# LoRa_Node_Schematic.net
KiCad netlist of a schematic drawn in EAGLE
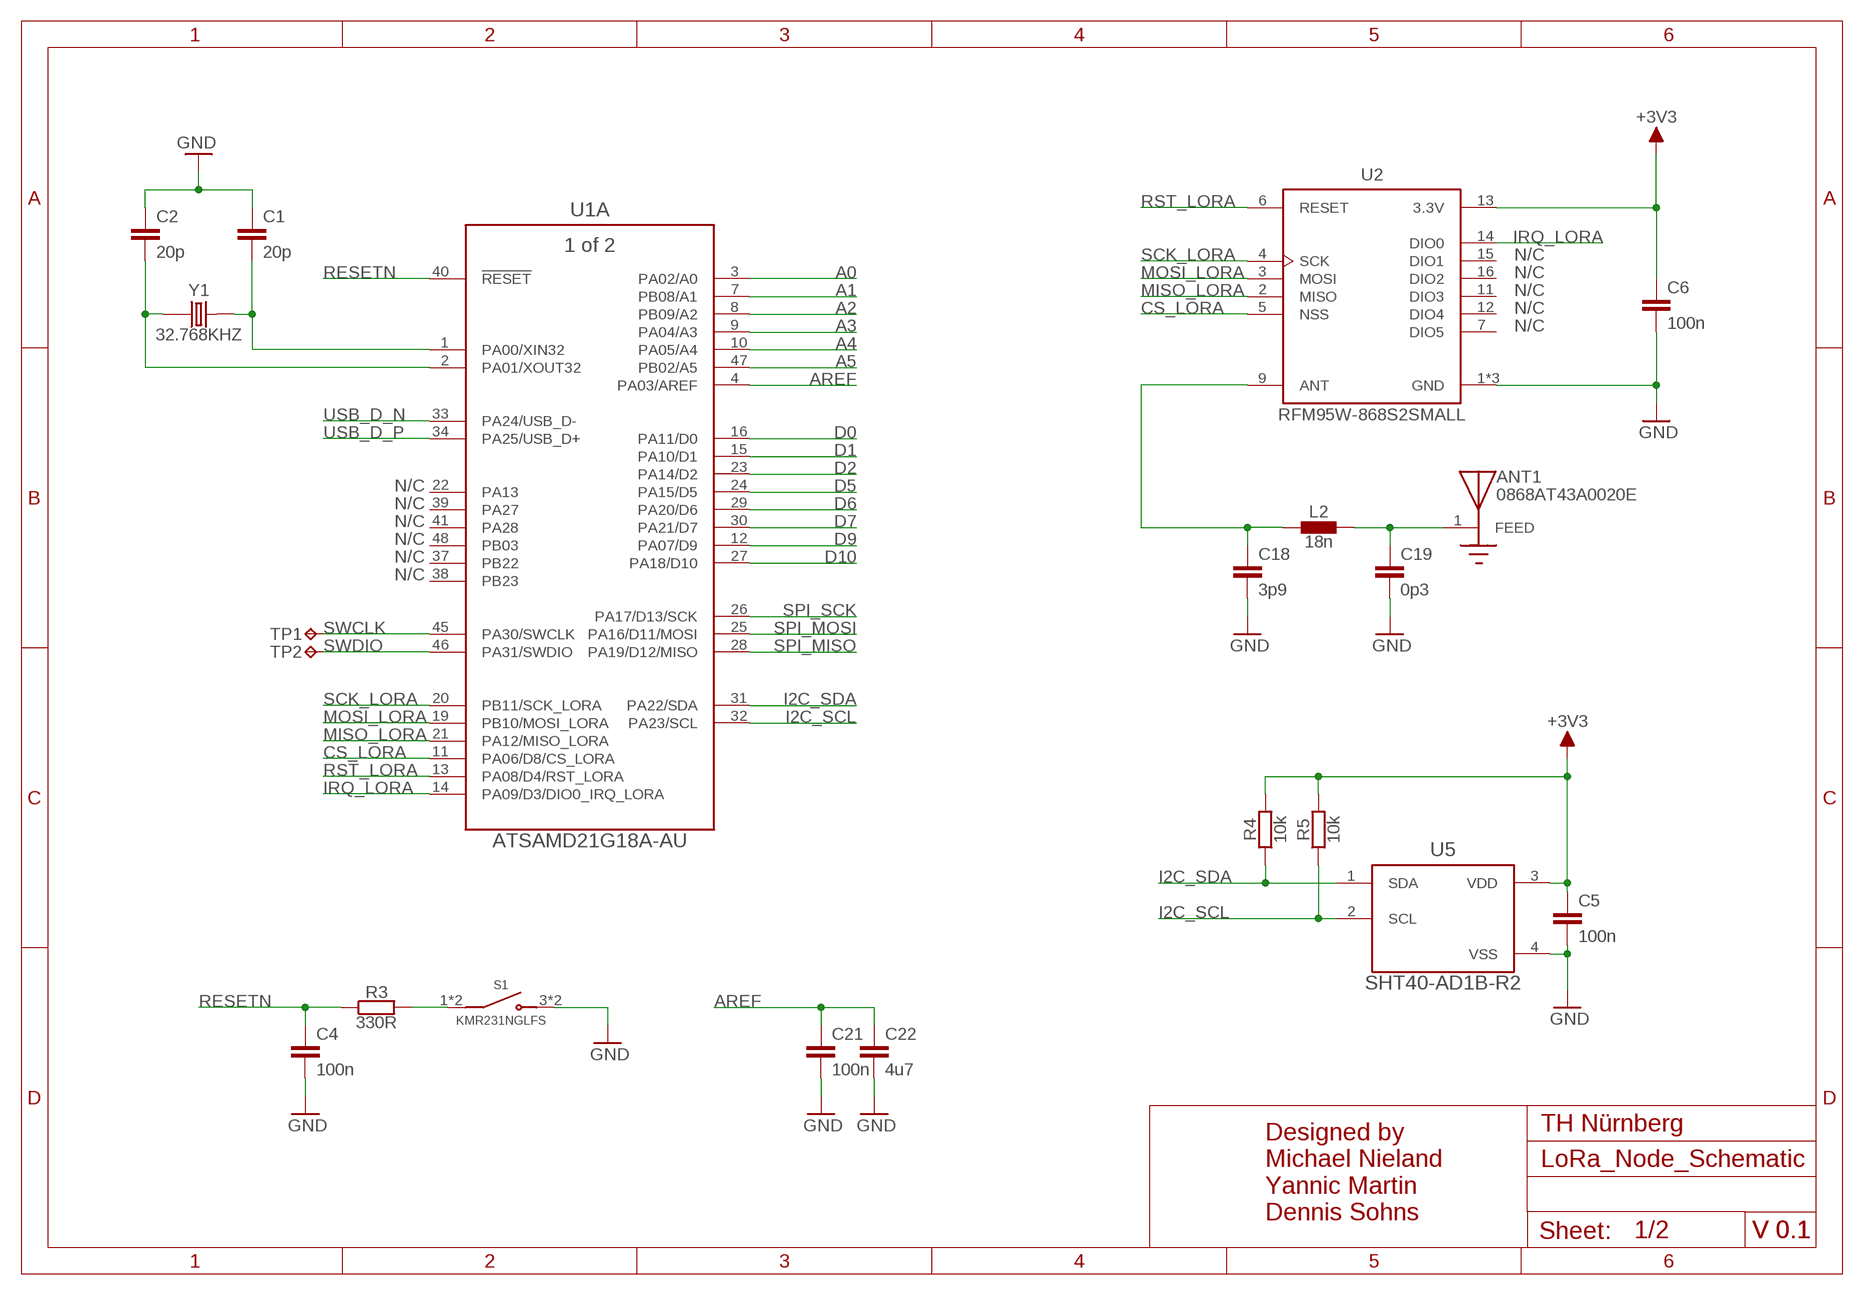
[diagram p0: schematic, sheet 1]
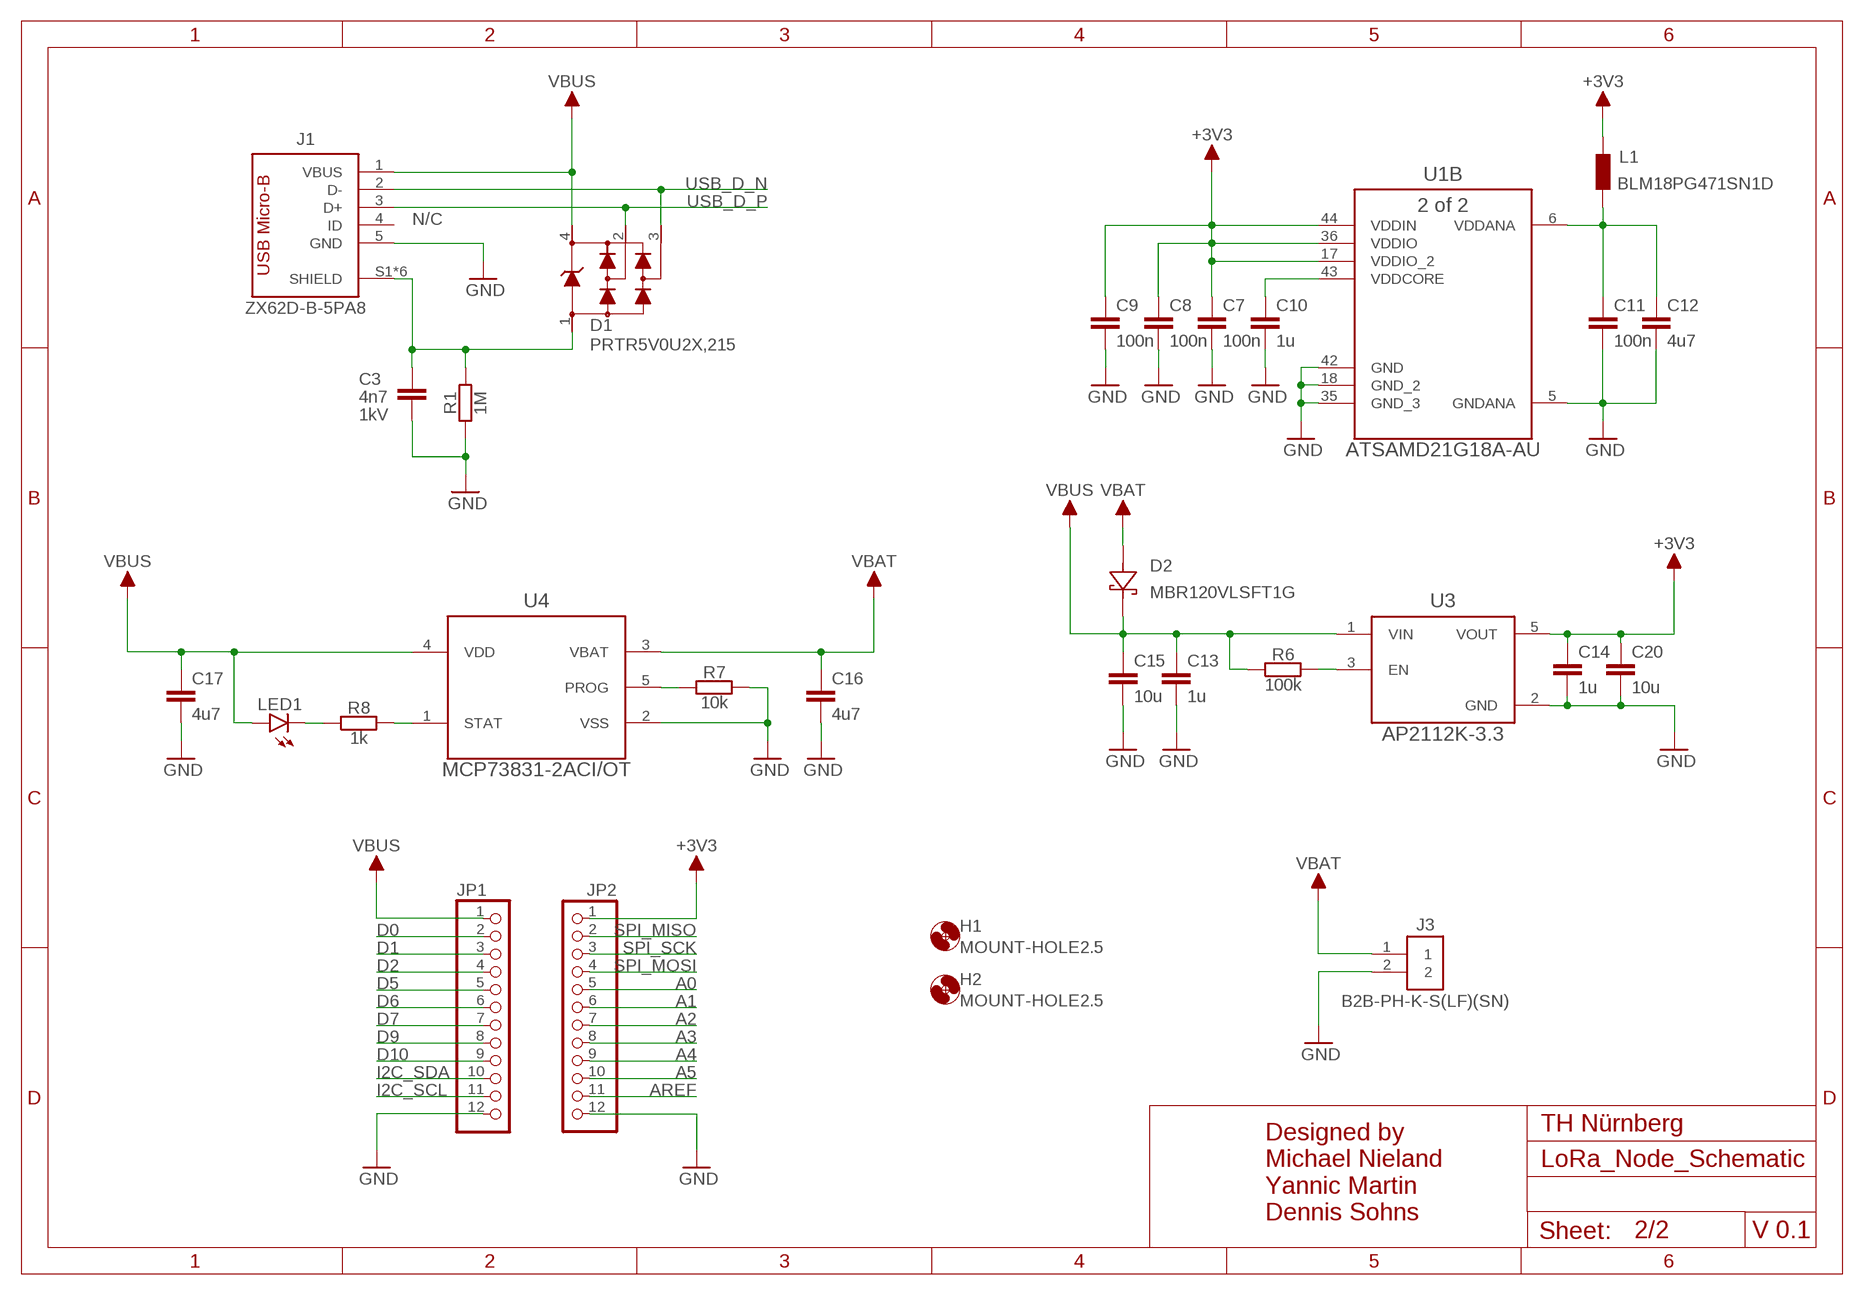
[diagram p1: schematic, sheet 2]

(export (version "E")
  (design (tool "Eeschema 10.0.6"))
  (components
    (comp (ref "C3")
      (value "4n7")
      (footprint "eagle-import:C0805")
      (fields (field (name "MANUFACTURER") "KEMET") (field (name "VOLTAGE") "1kV"))
      (libsource (lib "eagle-import") (part "C-EUC0805"))
    )
    (comp (ref "C7")
      (value "100n")
      (footprint "eagle-import:C0402")
      (libsource (lib "eagle-import") (part "C-EUC0402"))
    )
    (comp (ref "C8")
      (value "100n")
      (footprint "eagle-import:C0402")
      (libsource (lib "eagle-import") (part "C-EUC0402"))
    )
    (comp (ref "C9")
      (value "100n")
      (footprint "eagle-import:C0402")
      (libsource (lib "eagle-import") (part "C-EUC0402"))
    )
    (comp (ref "C10")
      (value "1u")
      (footprint "eagle-import:C0402")
      (libsource (lib "eagle-import") (part "C-EUC0402"))
    )
    (comp (ref "C11")
      (value "100n")
      (footprint "eagle-import:C0402")
      (libsource (lib "eagle-import") (part "C-EUC0402"))
    )
    (comp (ref "C12")
      (value "4u7")
      (footprint "eagle-import:C0603")
      (libsource (lib "eagle-import") (part "C-EUC0603"))
    )
    (comp (ref "C13")
      (value "1u")
      (footprint "eagle-import:C0402")
      (libsource (lib "eagle-import") (part "C-EUC0402"))
    )
    (comp (ref "C14")
      (value "1u")
      (footprint "eagle-import:C0402")
      (libsource (lib "eagle-import") (part "C-EUC0402"))
    )
    (comp (ref "C15")
      (value "10u")
      (footprint "eagle-import:C0603")
      (libsource (lib "eagle-import") (part "C-EUC0603"))
    )
    (comp (ref "C16")
      (value "4u7")
      (footprint "eagle-import:C0603")
      (libsource (lib "eagle-import") (part "C-EUC0603"))
    )
    (comp (ref "C17")
      (value "4u7")
      (footprint "eagle-import:C0603")
      (libsource (lib "eagle-import") (part "C-EUC0603"))
    )
    (comp (ref "C20")
      (value "10u")
      (footprint "eagle-import:C0603")
      (libsource (lib "eagle-import") (part "C-EUC0603"))
    )
    (comp (ref "D1")
      (value "PRTR5V0U2X,215")
      (footprint "eagle-import:SOT143B")
      (fields (field (name "MF") "Nexperia USA Inc."))
      (libsource (lib "eagle-import") (part "PRTR5V0U2X,215"))
    )
    (comp (ref "D2")
      (value "MBR120VLSFT1G")
      (footprint "eagle-import:SDO_SOD-123FL_ONS")
      (fields (field (name "COPYRIGHT") "Copyright (C) 2018 Accelerated Designs. All rights reserved"))
      (libsource (lib "eagle-import") (part "MBR120VLSFT1G"))
    )
    (comp (ref "H1")
      (value "MOUNT-HOLE2.5")
      (footprint "eagle-import:MICROBUILDER_MOUNTINGHOLE_2.5_PLATED")
      (libsource (lib "eagle-import") (part "MOUNT-HOLE2.5"))
    )
    (comp (ref "H2")
      (value "MOUNT-HOLE2.5")
      (footprint "eagle-import:MICROBUILDER_MOUNTINGHOLE_2.5_PLATED")
      (libsource (lib "eagle-import") (part "MOUNT-HOLE2.5"))
    )
    (comp (ref "J1")
      (value "ZX62D-B-5PA8")
      (footprint "eagle-import:HIROSE_ZX62D-B-5PA8")
      (fields (field (name "MF") "Hirose"))
      (libsource (lib "eagle-import") (part "ZX62D-B-5PA8"))
    )
    (comp (ref "J3")
      (value "B2B-PH-K-S(LF)(SN)")
      (footprint "eagle-import:JST_B2B-PH-K-S(LF)(SN)")
      (fields (field (name "MF") "JST Sales"))
      (libsource (lib "eagle-import") (part "B2B-PH-K-S(LF)(SN)"))
    )
    (comp (ref "JP1")
      (value "PINHD-1X12-CB")
      (footprint "eagle-import:1X12-CB")
      (libsource (lib "eagle-import") (part "PINHD-1X12-CB"))
    )
    (comp (ref "JP2")
      (value "PINHD-1X12-CB")
      (footprint "eagle-import:1X12-CB")
      (libsource (lib "eagle-import") (part "PINHD-1X12-CB"))
    )
    (comp (ref "L1")
      (value "BLM18PG471SN1D")
      (footprint "eagle-import:IND_BLM18_0603_MUR")
      (libsource (lib "eagle-import") (part "BLM18PG471SN1D"))
    )
    (comp (ref "LED1")
      (value "LEDCHIP-LED0805")
      (footprint "eagle-import:CHIP-LED0805")
      (libsource (lib "eagle-import") (part "LEDCHIP-LED0805"))
    )
    (comp (ref "R1")
      (value "1M")
      (footprint "eagle-import:R0402")
      (libsource (lib "eagle-import") (part "R-EU_R0402"))
    )
    (comp (ref "R6")
      (value "100k")
      (footprint "eagle-import:R0402")
      (libsource (lib "eagle-import") (part "R-EU_R0402"))
    )
    (comp (ref "R7")
      (value "10k")
      (footprint "eagle-import:R0402")
      (libsource (lib "eagle-import") (part "R-EU_R0402"))
    )
    (comp (ref "R8")
      (value "1k")
      (footprint "eagle-import:R0402")
      (libsource (lib "eagle-import") (part "R-EU_R0402"))
    )
    (comp (ref "U1")
      (value "ATSAMD21G18A-AU")
      (footprint "eagle-import:TQFP48_7X7MC_MCH")
      (fields (field (name "COPYRIGHT") "Copyright (C) 2018 Accelerated Designs. All rights reserved"))
      (libsource (lib "eagle-import") (part "ATSAMD21G18A-AU"))
    )
    (comp (ref "U3")
      (value "AP2112K-3.3")
      (footprint "eagle-import:SOT95P285X140-5N")
      (fields (field (name "MF") "Diodes Inc."))
      (libsource (lib "eagle-import") (part "AP2112K-3.3"))
    )
    (comp (ref "U4")
      (value "MCP73831-2ACI/OT")
      (footprint "eagle-import:SOT95P280X145-5N")
      (fields (field (name "MF") "Microchip"))
      (libsource (lib "eagle-import") (part "MCP73831-2ACI/OT"))
    )
    (comp (ref "ANT1")
      (value "0868AT43A0020E")
      (footprint "eagle-import:XCVR_0868AT43A0020E")
      (fields (field (name "DIGI-KEY_PART_NUMBER") "712-1399-1-ND") (field (name "MF") "Johanson Technology"))
      (libsource (lib "eagle-import") (part "0868AT43A0020E"))
    )
    (comp (ref "C1")
      (value "20p")
      (footprint "eagle-import:C0402")
      (libsource (lib "eagle-import") (part "C-EUC0402"))
    )
    (comp (ref "C2")
      (value "20p")
      (footprint "eagle-import:C0402")
      (libsource (lib "eagle-import") (part "C-EUC0402"))
    )
    (comp (ref "C4")
      (value "100n")
      (footprint "eagle-import:C0402")
      (libsource (lib "eagle-import") (part "C-EUC0402"))
    )
    (comp (ref "C5")
      (value "100n")
      (footprint "eagle-import:C0402")
      (libsource (lib "eagle-import") (part "C-EUC0402"))
    )
    (comp (ref "C6")
      (value "100n")
      (footprint "eagle-import:C0402")
      (libsource (lib "eagle-import") (part "C-EUC0402"))
    )
    (comp (ref "C18")
      (value "3p9")
      (footprint "eagle-import:C0402")
      (fields (field (name "MANUFACTURER") "Johanson Technology"))
      (libsource (lib "eagle-import") (part "C-EUC0402"))
    )
    (comp (ref "C19")
      (value "0p3")
      (footprint "eagle-import:C0402")
      (fields (field (name "MANUFACTURER") "Johanson Technology"))
      (libsource (lib "eagle-import") (part "C-EUC0402"))
    )
    (comp (ref "C21")
      (value "100n")
      (footprint "eagle-import:C0402")
      (libsource (lib "eagle-import") (part "C-EUC0402"))
    )
    (comp (ref "C22")
      (value "4u7")
      (footprint "eagle-import:C0603")
      (libsource (lib "eagle-import") (part "C-EUC0603"))
    )
    (comp (ref "L2")
      (value "18n")
      (footprint "eagle-import:R0402")
      (fields (field (name "MANUFACTURER") "Johanson Technology"))
      (libsource (lib "eagle-import") (part "INDUCTOR_0402_SMD"))
    )
    (comp (ref "R3")
      (value "330R")
      (footprint "eagle-import:R0402")
      (libsource (lib "eagle-import") (part "R-EU_R0402"))
    )
    (comp (ref "R4")
      (value "10k")
      (footprint "eagle-import:R0402")
      (libsource (lib "eagle-import") (part "R-EU_R0402"))
    )
    (comp (ref "R5")
      (value "10k")
      (footprint "eagle-import:R0402")
      (libsource (lib "eagle-import") (part "R-EU_R0402"))
    )
    (comp (ref "S1")
      (value "KMR231NGLFS")
      (footprint "eagle-import:SW_KMR231NGLFS")
      (fields (field (name "MF") "C&K Components"))
      (libsource (lib "eagle-import") (part "KMR231NGLFS"))
    )
    (comp (ref "TP1")
      (value "TPTP10R")
      (footprint "eagle-import:TP10R")
      (libsource (lib "eagle-import") (part "TPTP10R"))
    )
    (comp (ref "TP2")
      (value "TPTP10R")
      (footprint "eagle-import:TP10R")
      (libsource (lib "eagle-import") (part "TPTP10R"))
    )
    (comp (ref "U2")
      (value "RFM95W-868S2SMALL")
      (footprint "eagle-import:MICROBUILDER_RFMHCW_SMT")
      (libsource (lib "eagle-import") (part "RFM95W-868S2SMALL"))
    )
    (comp (ref "U5")
      (value "SHT40-AD1B-R2")
      (footprint "eagle-import:SHT4X_SEN")
      (fields (field (name "COPYRIGHT") "Copyright (C) 2018 Accelerated Designs. All rights reserved"))
      (libsource (lib "eagle-import") (part "SHT40-AD1B-R2"))
    )
    (comp (ref "Y1")
      (value "32.768KHZ")
      (footprint "eagle-import:XTAL_ABS07-32.768KHZ-T")
      (fields
        (field (name "DIGI-KEY_PART_NUMBER") "535-9542-1-ND")
        (field (name "MF") "Abracon")
        (field (name "MP") "ABS07-32.768KHZ-T")
      )
      (libsource (lib "eagle-import") (part "ABS07-32.768KHZ-T"))
    )
  )
  (nets
    (net (code "1") (name "+3V3") (class "Default")
      (node (ref "C14") (pin "1") (pinfunction "1_1") (pintype "passive"))
      (node (ref "C20") (pin "1") (pinfunction "1_1") (pintype "passive"))
      (node (ref "C5") (pin "1") (pinfunction "1_1") (pintype "passive"))
      (node (ref "C6") (pin "1") (pinfunction "1_1") (pintype "passive"))
      (node (ref "C7") (pin "1") (pinfunction "1_1") (pintype "passive"))
      (node (ref "C8") (pin "1") (pinfunction "1_1") (pintype "passive"))
      (node (ref "C9") (pin "1") (pinfunction "1_1") (pintype "passive"))
      (node (ref "JP2") (pin "1") (pinfunction "1_1") (pintype "passive"))
      (node (ref "L1") (pin "1") (pinfunction "1_1") (pintype "passive"))
      (node (ref "R4") (pin "2") (pinfunction "2_2") (pintype "passive"))
      (node (ref "R5") (pin "2") (pinfunction "2_2") (pintype "passive"))
      (node (ref "U1") (pin "17") (pinfunction "VDDIO_2_17") (pintype "power_in"))
      (node (ref "U1") (pin "36") (pinfunction "VDDIO_36") (pintype "power_in"))
      (node (ref "U1") (pin "44") (pinfunction "VDDIN_44") (pintype "power_in"))
      (node (ref "U2") (pin "13") (pinfunction "3.3V_13") (pintype "power_in"))
      (node (ref "U3") (pin "5") (pinfunction "VOUT_5") (pintype "power_in"))
      (node (ref "U5") (pin "3") (pinfunction "VDD_3") (pintype "power_in"))
    )
    (net (code "2") (name "A0") (class "Default")
      (node (ref "JP2") (pin "5") (pinfunction "5_5") (pintype "passive"))
      (node (ref "U1") (pin "3") (pinfunction "PA02/A0_3") (pintype "bidirectional"))
    )
    (net (code "3") (name "A1") (class "Default")
      (node (ref "JP2") (pin "6") (pinfunction "6_6") (pintype "passive"))
      (node (ref "U1") (pin "7") (pinfunction "PB08/A1_7") (pintype "bidirectional"))
    )
    (net (code "4") (name "A2") (class "Default")
      (node (ref "JP2") (pin "7") (pinfunction "7_7") (pintype "passive"))
      (node (ref "U1") (pin "8") (pinfunction "PB09/A2_8") (pintype "bidirectional"))
    )
    (net (code "5") (name "A3") (class "Default")
      (node (ref "JP2") (pin "8") (pinfunction "8_8") (pintype "passive"))
      (node (ref "U1") (pin "9") (pinfunction "PA04/A3_9") (pintype "bidirectional"))
    )
    (net (code "6") (name "A4") (class "Default")
      (node (ref "JP2") (pin "9") (pinfunction "9_9") (pintype "passive"))
      (node (ref "U1") (pin "10") (pinfunction "PA05/A4_10") (pintype "bidirectional"))
    )
    (net (code "7") (name "A5") (class "Default")
      (node (ref "JP2") (pin "10") (pinfunction "10_10") (pintype "passive"))
      (node (ref "U1") (pin "47") (pinfunction "PB02/A5_47") (pintype "bidirectional"))
    )
    (net (code "8") (name "AREF") (class "Default")
      (node (ref "C21") (pin "1") (pinfunction "1_1") (pintype "passive"))
      (node (ref "C22") (pin "1") (pinfunction "1_1") (pintype "passive"))
      (node (ref "JP2") (pin "11") (pinfunction "11_11") (pintype "passive"))
      (node (ref "U1") (pin "4") (pinfunction "PA03/AREF_4") (pintype "bidirectional"))
    )
    (net (code "9") (name "CS_LORA") (class "Default")
      (node (ref "U1") (pin "11") (pinfunction "PA06/D8/CS_LORA_11") (pintype "bidirectional"))
      (node (ref "U2") (pin "5") (pinfunction "NSS_5") (pintype "input"))
    )
    (net (code "10") (name "D0") (class "Default")
      (node (ref "JP1") (pin "2") (pinfunction "2_2") (pintype "passive"))
      (node (ref "U1") (pin "16") (pinfunction "PA11/D0_16") (pintype "bidirectional"))
    )
    (net (code "11") (name "D1") (class "Default")
      (node (ref "JP1") (pin "3") (pinfunction "3_3") (pintype "passive"))
      (node (ref "U1") (pin "15") (pinfunction "PA10/D1_15") (pintype "bidirectional"))
    )
    (net (code "12") (name "D2") (class "Default")
      (node (ref "JP1") (pin "4") (pinfunction "4_4") (pintype "passive"))
      (node (ref "U1") (pin "23") (pinfunction "PA14/D2_23") (pintype "bidirectional"))
    )
    (net (code "13") (name "D5") (class "Default")
      (node (ref "JP1") (pin "5") (pinfunction "5_5") (pintype "passive"))
      (node (ref "U1") (pin "24") (pinfunction "PA15/D5_24") (pintype "bidirectional"))
    )
    (net (code "14") (name "D6") (class "Default")
      (node (ref "JP1") (pin "6") (pinfunction "6_6") (pintype "passive"))
      (node (ref "U1") (pin "29") (pinfunction "PA20/D6_29") (pintype "bidirectional"))
    )
    (net (code "15") (name "D7") (class "Default")
      (node (ref "JP1") (pin "7") (pinfunction "7_7") (pintype "passive"))
      (node (ref "U1") (pin "30") (pinfunction "PA21/D7_30") (pintype "bidirectional"))
    )
    (net (code "16") (name "D9") (class "Default")
      (node (ref "JP1") (pin "8") (pinfunction "8_8") (pintype "passive"))
      (node (ref "U1") (pin "12") (pinfunction "PA07/D9_12") (pintype "bidirectional"))
    )
    (net (code "17") (name "D10") (class "Default")
      (node (ref "JP1") (pin "9") (pinfunction "9_9") (pintype "passive"))
      (node (ref "U1") (pin "27") (pinfunction "PA18/D10_27") (pintype "bidirectional"))
    )
    (net (code "18") (name "GND") (class "Default")
      (node (ref "C1") (pin "1") (pinfunction "1_1") (pintype "passive"))
      (node (ref "C10") (pin "2") (pinfunction "2_2") (pintype "passive"))
      (node (ref "C11") (pin "2") (pinfunction "2_2") (pintype "passive"))
      (node (ref "C12") (pin "2") (pinfunction "2_2") (pintype "passive"))
      (node (ref "C13") (pin "2") (pinfunction "2_2") (pintype "passive"))
      (node (ref "C14") (pin "2") (pinfunction "2_2") (pintype "passive"))
      (node (ref "C15") (pin "2") (pinfunction "2_2") (pintype "passive"))
      (node (ref "C16") (pin "2") (pinfunction "2_2") (pintype "passive"))
      (node (ref "C17") (pin "2") (pinfunction "2_2") (pintype "passive"))
      (node (ref "C18") (pin "2") (pinfunction "2_2") (pintype "passive"))
      (node (ref "C19") (pin "2") (pinfunction "2_2") (pintype "passive"))
      (node (ref "C2") (pin "1") (pinfunction "1_1") (pintype "passive"))
      (node (ref "C20") (pin "2") (pinfunction "2_2") (pintype "passive"))
      (node (ref "C21") (pin "2") (pinfunction "2_2") (pintype "passive"))
      (node (ref "C22") (pin "2") (pinfunction "2_2") (pintype "passive"))
      (node (ref "C3") (pin "2") (pinfunction "2_2") (pintype "passive"))
      (node (ref "C4") (pin "2") (pinfunction "2_2") (pintype "passive"))
      (node (ref "C5") (pin "2") (pinfunction "2_2") (pintype "passive"))
      (node (ref "C6") (pin "2") (pinfunction "2_2") (pintype "passive"))
      (node (ref "C7") (pin "2") (pinfunction "2_2") (pintype "passive"))
      (node (ref "C8") (pin "2") (pinfunction "2_2") (pintype "passive"))
      (node (ref "C9") (pin "2") (pinfunction "2_2") (pintype "passive"))
      (node (ref "J1") (pin "5") (pinfunction "GND_5") (pintype "passive"))
      (node (ref "J3") (pin "2") (pinfunction "2_2") (pintype "passive"))
      (node (ref "JP1") (pin "12") (pinfunction "12_12") (pintype "passive"))
      (node (ref "JP2") (pin "12") (pinfunction "12_12") (pintype "passive"))
      (node (ref "R1") (pin "1") (pinfunction "1_1") (pintype "passive"))
      (node (ref "R7") (pin "2") (pinfunction "2_2") (pintype "passive"))
      (node (ref "S1") (pin "3") (pinfunction "NO_3") (pintype "passive"))
      (node (ref "S1") (pin "4") (pinfunction "NO_4") (pintype "passive"))
      (node (ref "U1") (pin "18") (pinfunction "GND_2_18") (pintype "passive"))
      (node (ref "U1") (pin "35") (pinfunction "GND_3_35") (pintype "passive"))
      (node (ref "U1") (pin "42") (pinfunction "GND_42") (pintype "passive"))
      (node (ref "U1") (pin "5") (pinfunction "GNDANA_5") (pintype "passive"))
      (node (ref "U2") (pin "1") (pinfunction "GND_1") (pintype "power_in"))
      (node (ref "U2") (pin "10") (pinfunction "GND_10") (pintype "power_in"))
      (node (ref "U2") (pin "8") (pinfunction "GND_8") (pintype "power_in"))
      (node (ref "U3") (pin "2") (pinfunction "GND_2") (pintype "power_in"))
      (node (ref "U4") (pin "2") (pinfunction "VSS_2") (pintype "power_in"))
      (node (ref "U5") (pin "4") (pinfunction "VSS_4") (pintype "passive"))
    )
    (net (code "19") (name "I2C_SCL") (class "Default")
      (node (ref "JP1") (pin "11") (pinfunction "11_11") (pintype "passive"))
      (node (ref "R5") (pin "1") (pinfunction "1_1") (pintype "passive"))
      (node (ref "U1") (pin "32") (pinfunction "PA23/SCL_32") (pintype "bidirectional"))
      (node (ref "U5") (pin "2") (pinfunction "SCL_2") (pintype "input"))
    )
    (net (code "20") (name "I2C_SDA") (class "Default")
      (node (ref "JP1") (pin "10") (pinfunction "10_10") (pintype "passive"))
      (node (ref "R4") (pin "1") (pinfunction "1_1") (pintype "passive"))
      (node (ref "U1") (pin "31") (pinfunction "PA22/SDA_31") (pintype "bidirectional"))
      (node (ref "U5") (pin "1") (pinfunction "SDA_1") (pintype "bidirectional"))
    )
    (net (code "21") (name "IRQ_LORA") (class "Default")
      (node (ref "U1") (pin "14") (pinfunction "PA09/D3/DIO0_IRQ_LORA_14") (pintype "bidirectional"))
      (node (ref "U2") (pin "14") (pinfunction "DIO0_14") (pintype "bidirectional"))
    )
    (net (code "22") (name "MISO_LORA") (class "Default")
      (node (ref "U1") (pin "21") (pinfunction "PA12/MISO_LORA_21") (pintype "bidirectional"))
      (node (ref "U2") (pin "2") (pinfunction "MISO_2") (pintype "output"))
    )
    (net (code "23") (name "MOSI_LORA") (class "Default")
      (node (ref "U1") (pin "19") (pinfunction "PB10/MOSI_LORA_19") (pintype "bidirectional"))
      (node (ref "U2") (pin "3") (pinfunction "MOSI_3") (pintype "input"))
    )
    (net (code "24") (name "Net-(ANT1-FEED)") (class "Default")
      (node (ref "ANT1") (pin "1") (pinfunction "FEED_1") (pintype "input"))
      (node (ref "C19") (pin "1") (pinfunction "1_1") (pintype "passive"))
      (node (ref "L2") (pin "2") (pinfunction "2_2") (pintype "passive"))
    )
    (net (code "25") (name "Net-(D1-P$1)") (class "Default")
      (node (ref "C3") (pin "1") (pinfunction "1_1") (pintype "passive"))
      (node (ref "D1") (pin "1") (pinfunction "P$1_1") (pintype "passive"))
      (node (ref "J1") (pin "S1") (pinfunction "SHIELD_S1") (pintype "power_in"))
      (node (ref "J1") (pin "S2") (pinfunction "SHIELD_S2") (pintype "power_in"))
      (node (ref "J1") (pin "S3") (pinfunction "SHIELD_S3") (pintype "power_in"))
      (node (ref "J1") (pin "S4") (pinfunction "SHIELD_S4") (pintype "power_in"))
      (node (ref "J1") (pin "S5") (pinfunction "SHIELD_S5") (pintype "power_in"))
      (node (ref "J1") (pin "S6") (pinfunction "SHIELD_S6") (pintype "power_in"))
      (node (ref "R1") (pin "2") (pinfunction "2_2") (pintype "passive"))
    )
    (net (code "26") (name "Net-(LED1-PadC)") (class "Default")
      (node (ref "LED1") (pin "C") (pinfunction "C_C") (pintype "passive"))
      (node (ref "R8") (pin "1") (pinfunction "1_1") (pintype "passive"))
    )
    (net (code "27") (name "Net-(R3-Pad2)") (class "Default")
      (node (ref "R3") (pin "2") (pinfunction "2_2") (pintype "passive"))
      (node (ref "S1") (pin "1") (pinfunction "COM_1") (pintype "passive"))
      (node (ref "S1") (pin "2") (pinfunction "COM_2") (pintype "passive"))
    )
    (net (code "28") (name "Net-(U1A-PA00{slash}XIN32)") (class "Default")
      (node (ref "C1") (pin "2") (pinfunction "2_2") (pintype "passive"))
      (node (ref "U1") (pin "1") (pinfunction "PA00/XIN32_1") (pintype "bidirectional"))
      (node (ref "Y1") (pin "2") (pinfunction "2_2") (pintype "passive"))
    )
    (net (code "29") (name "Net-(U1A-PA01{slash}XOUT32)") (class "Default")
      (node (ref "C2") (pin "2") (pinfunction "2_2") (pintype "passive"))
      (node (ref "U1") (pin "2") (pinfunction "PA01/XOUT32_2") (pintype "bidirectional"))
      (node (ref "Y1") (pin "1") (pinfunction "1_1") (pintype "passive"))
    )
    (net (code "30") (name "Net-(U1B-VDDANA)") (class "Default")
      (node (ref "C11") (pin "1") (pinfunction "1_1") (pintype "passive"))
      (node (ref "C12") (pin "1") (pinfunction "1_1") (pintype "passive"))
      (node (ref "L1") (pin "2") (pinfunction "2_2") (pintype "passive"))
      (node (ref "U1") (pin "6") (pinfunction "VDDANA_6") (pintype "power_in"))
    )
    (net (code "31") (name "Net-(U1B-VDDCORE)") (class "Default")
      (node (ref "C10") (pin "1") (pinfunction "1_1") (pintype "passive"))
      (node (ref "U1") (pin "43") (pinfunction "VDDCORE_43") (pintype "power_in"))
    )
    (net (code "32") (name "Net-(U2-ANT)") (class "Default")
      (node (ref "C18") (pin "1") (pinfunction "1_1") (pintype "passive"))
      (node (ref "L2") (pin "1") (pinfunction "1_1") (pintype "passive"))
      (node (ref "U2") (pin "9") (pinfunction "ANT_9") (pintype "bidirectional"))
    )
    (net (code "33") (name "Net-(U3-EN)") (class "Default")
      (node (ref "R6") (pin "2") (pinfunction "2_2") (pintype "passive"))
      (node (ref "U3") (pin "3") (pinfunction "EN_3") (pintype "input"))
    )
    (net (code "34") (name "Net-(U4-PROG)") (class "Default")
      (node (ref "R7") (pin "1") (pinfunction "1_1") (pintype "passive"))
      (node (ref "U4") (pin "5") (pinfunction "PROG_5") (pintype "input"))
    )
    (net (code "35") (name "Net-(U4-STAT)") (class "Default")
      (node (ref "R8") (pin "2") (pinfunction "2_2") (pintype "passive"))
      (node (ref "U4") (pin "1") (pinfunction "STAT_1") (pintype "output"))
    )
    (net (code "36") (name "RESETN") (class "Default")
      (node (ref "C4") (pin "1") (pinfunction "1_1") (pintype "passive"))
      (node (ref "R3") (pin "1") (pinfunction "1_1") (pintype "passive"))
      (node (ref "U1") (pin "40") (pinfunction "~{RESET}_40") (pintype "passive"))
    )
    (net (code "37") (name "RST_LORA") (class "Default")
      (node (ref "U1") (pin "13") (pinfunction "PA08/D4/RST_LORA_13") (pintype "bidirectional"))
      (node (ref "U2") (pin "6") (pinfunction "RESET_6") (pintype "bidirectional"))
    )
    (net (code "38") (name "SCK_LORA") (class "Default")
      (node (ref "U1") (pin "20") (pinfunction "PB11/SCK_LORA_20") (pintype "bidirectional"))
      (node (ref "U2") (pin "4") (pinfunction "SCK_4") (pintype "input"))
    )
    (net (code "39") (name "SPI_MISO") (class "Default")
      (node (ref "JP2") (pin "2") (pinfunction "2_2") (pintype "passive"))
      (node (ref "U1") (pin "28") (pinfunction "PA19/D12/MISO_28") (pintype "bidirectional"))
    )
    (net (code "40") (name "SPI_MOSI") (class "Default")
      (node (ref "JP2") (pin "4") (pinfunction "4_4") (pintype "passive"))
      (node (ref "U1") (pin "25") (pinfunction "PA16/D11/MOSI_25") (pintype "bidirectional"))
    )
    (net (code "41") (name "SPI_SCK") (class "Default")
      (node (ref "JP2") (pin "3") (pinfunction "3_3") (pintype "passive"))
      (node (ref "U1") (pin "26") (pinfunction "PA17/D13/SCK_26") (pintype "bidirectional"))
    )
    (net (code "42") (name "SWCLK") (class "Default")
      (node (ref "TP1") (pin "TP") (pinfunction "TP_TP") (pintype "input"))
      (node (ref "U1") (pin "45") (pinfunction "PA30/SWCLK_45") (pintype "bidirectional"))
    )
    (net (code "43") (name "SWDIO") (class "Default")
      (node (ref "TP2") (pin "TP") (pinfunction "TP_TP") (pintype "input"))
      (node (ref "U1") (pin "46") (pinfunction "PA31/SWDIO_46") (pintype "bidirectional"))
    )
    (net (code "44") (name "USB_D_N") (class "Default")
      (node (ref "D1") (pin "3") (pinfunction "P$3_3") (pintype "passive"))
      (node (ref "J1") (pin "2") (pinfunction "D-_2") (pintype "passive"))
      (node (ref "U1") (pin "33") (pinfunction "PA24/USB_D-_33") (pintype "bidirectional"))
    )
    (net (code "45") (name "USB_D_P") (class "Default")
      (node (ref "D1") (pin "2") (pinfunction "P$2_2") (pintype "passive"))
      (node (ref "J1") (pin "3") (pinfunction "D+_3") (pintype "passive"))
      (node (ref "U1") (pin "34") (pinfunction "PA25/USB_D+_34") (pintype "bidirectional"))
    )
    (net (code "46") (name "VBAT") (class "Default")
      (node (ref "C16") (pin "1") (pinfunction "1_1") (pintype "passive"))
      (node (ref "D2") (pin "2") (pinfunction "12_2") (pintype "passive"))
      (node (ref "J3") (pin "1") (pinfunction "1_1") (pintype "passive"))
      (node (ref "U4") (pin "3") (pinfunction "VBAT_3") (pintype "power_in"))
    )
    (net (code "47") (name "VBUS") (class "Default")
      (node (ref "C13") (pin "1") (pinfunction "1_1") (pintype "passive"))
      (node (ref "C15") (pin "1") (pinfunction "1_1") (pintype "passive"))
      (node (ref "C17") (pin "1") (pinfunction "1_1") (pintype "passive"))
      (node (ref "D1") (pin "4") (pinfunction "P$4_4") (pintype "passive"))
      (node (ref "D2") (pin "1") (pinfunction "11_1") (pintype "passive"))
      (node (ref "J1") (pin "1") (pinfunction "VBUS_1") (pintype "passive"))
      (node (ref "JP1") (pin "1") (pinfunction "1_1") (pintype "passive"))
      (node (ref "LED1") (pin "A") (pinfunction "A_A") (pintype "passive"))
      (node (ref "R6") (pin "1") (pinfunction "1_1") (pintype "passive"))
      (node (ref "U3") (pin "1") (pinfunction "VIN_1") (pintype "power_in"))
      (node (ref "U4") (pin "4") (pinfunction "VDD_4") (pintype "power_in"))
    )
    (net (code "48") (name "unconnected-(J1-ID-Pad4)") (class "Default")
      (node (ref "J1") (pin "4") (pinfunction "ID_4") (pintype "passive"))
    )
    (net (code "49") (name "unconnected-(U1A-PA13-Pad22)") (class "Default")
      (node (ref "U1") (pin "22") (pinfunction "PA13_22") (pintype "bidirectional"))
    )
    (net (code "50") (name "unconnected-(U1A-PA27-Pad39)") (class "Default")
      (node (ref "U1") (pin "39") (pinfunction "PA27_39") (pintype "bidirectional"))
    )
    (net (code "51") (name "unconnected-(U1A-PA28-Pad41)") (class "Default")
      (node (ref "U1") (pin "41") (pinfunction "PA28_41") (pintype "bidirectional"))
    )
    (net (code "52") (name "unconnected-(U1A-PB03-Pad48)") (class "Default")
      (node (ref "U1") (pin "48") (pinfunction "PB03_48") (pintype "bidirectional"))
    )
    (net (code "53") (name "unconnected-(U1A-PB22-Pad37)") (class "Default")
      (node (ref "U1") (pin "37") (pinfunction "PB22_37") (pintype "bidirectional"))
    )
    (net (code "54") (name "unconnected-(U1A-PB23-Pad38)") (class "Default")
      (node (ref "U1") (pin "38") (pinfunction "PB23_38") (pintype "bidirectional"))
    )
    (net (code "55") (name "unconnected-(U2-DIO1-Pad15)") (class "Default")
      (node (ref "U2") (pin "15") (pinfunction "DIO1_15") (pintype "bidirectional"))
    )
    (net (code "56") (name "unconnected-(U2-DIO2-Pad16)") (class "Default")
      (node (ref "U2") (pin "16") (pinfunction "DIO2_16") (pintype "bidirectional"))
    )
    (net (code "57") (name "unconnected-(U2-DIO3-Pad11)") (class "Default")
      (node (ref "U2") (pin "11") (pinfunction "DIO3_11") (pintype "bidirectional"))
    )
    (net (code "58") (name "unconnected-(U2-DIO4-Pad12)") (class "Default")
      (node (ref "U2") (pin "12") (pinfunction "DIO4_12") (pintype "bidirectional"))
    )
    (net (code "59") (name "unconnected-(U2-DIO5-Pad7)") (class "Default")
      (node (ref "U2") (pin "7") (pinfunction "DIO5_7") (pintype "bidirectional"))
    )
  )
)
